# DRL.net
KiCad netlist of a schematic drawn in EAGLE
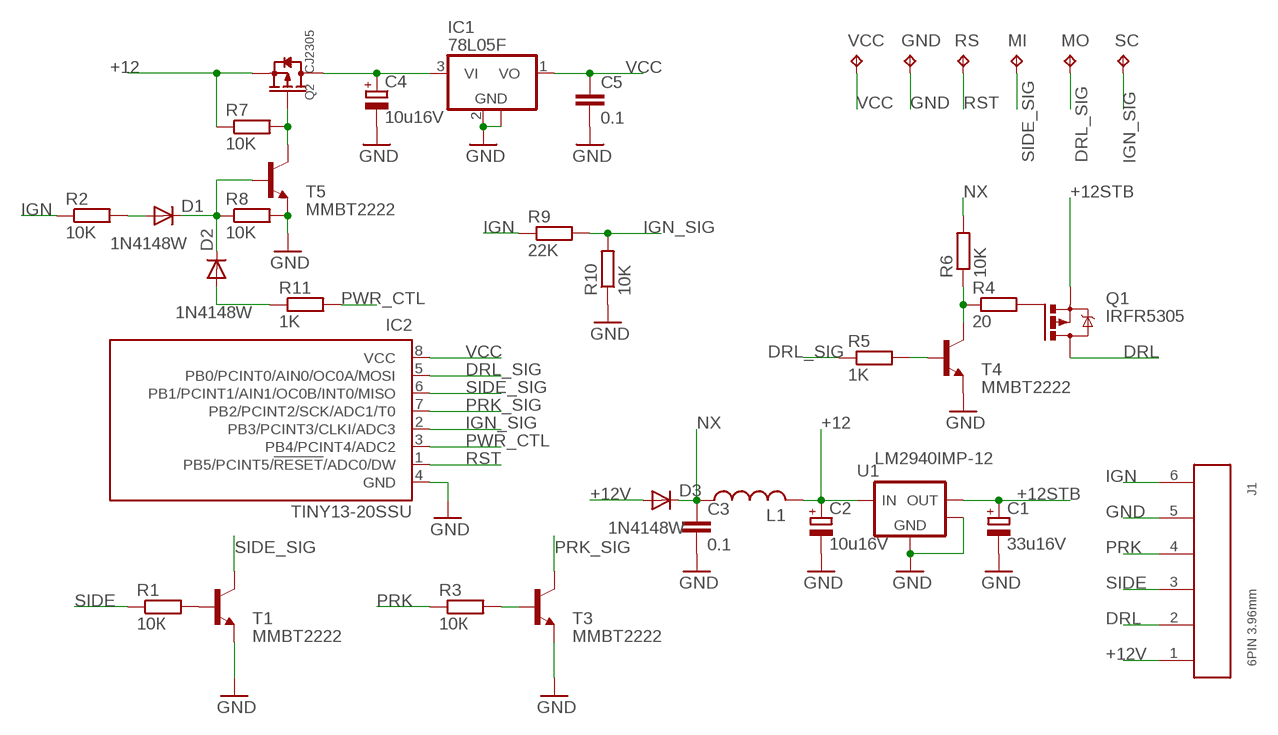
[diagram p0: schematic, sheet 1]

(export (version "E")
  (design (tool "Eeschema 10.0.6"))
  (components
    (comp (ref "C1")
      (value "33u16V")
      (footprint "eagle-import:SMC_B")
      (libsource (lib "eagle-import") (part "CPOL-EUSMCB"))
    )
    (comp (ref "C2")
      (value "10u16V")
      (footprint "eagle-import:SMC_B")
      (libsource (lib "eagle-import") (part "CPOL-EUSMCB"))
    )
    (comp (ref "C3")
      (value "0.1")
      (footprint "eagle-import:C0805")
      (libsource (lib "eagle-import") (part "C-EUC0805"))
    )
    (comp (ref "C4")
      (value "10u16V")
      (footprint "eagle-import:SMC_B")
      (libsource (lib "eagle-import") (part "CPOL-EUSMCB"))
    )
    (comp (ref "C5")
      (value "0.1")
      (footprint "eagle-import:C0805")
      (libsource (lib "eagle-import") (part "C-EUC0805"))
    )
    (comp (ref "D1")
      (value "1N4148W")
      (footprint "eagle-import:DO214AC")
      (libsource (lib "eagle-import") (part "DIODE-DO214AC"))
    )
    (comp (ref "D2")
      (value "1N4148W")
      (footprint "eagle-import:DO214AC")
      (libsource (lib "eagle-import") (part "DIODE-DO214AC"))
    )
    (comp (ref "D3")
      (value "1N4148W")
      (footprint "eagle-import:DO214AC")
      (libsource (lib "eagle-import") (part "DIODE-DO214AC"))
    )
    (comp (ref "GND")
      (value "TPB2,54")
      (footprint "eagle-import:B2,54")
      (libsource (lib "eagle-import") (part "TPB2,54"))
    )
    (comp (ref "IC1")
      (value "78L05F")
      (footprint "eagle-import:SOT89")
      (libsource (lib "eagle-import") (part "78LF05"))
    )
    (comp (ref "IC2")
      (value "TINY13-20SSU")
      (footprint "eagle-import:8S1")
      (fields (field (name "MPN") "ATTINY13-20SSU"))
      (libsource (lib "eagle-import") (part "TINY13SSU-20"))
    )
    (comp (ref "J1")
      (value "6PIN 3.96mm")
      (footprint "eagle-import:645006114822")
      (libsource (lib "eagle-import") (part "645006114822"))
    )
    (comp (ref "L1")
      (value "L-USL5038P")
      (footprint "eagle-import:L5038P")
      (libsource (lib "eagle-import") (part "L-USL5038P"))
    )
    (comp (ref "MI")
      (value "TPB2,54")
      (footprint "eagle-import:B2,54")
      (libsource (lib "eagle-import") (part "TPB2,54"))
    )
    (comp (ref "MO")
      (value "TPB2,54")
      (footprint "eagle-import:B2,54")
      (libsource (lib "eagle-import") (part "TPB2,54"))
    )
    (comp (ref "Q1")
      (value "IRFR5305")
      (footprint "eagle-import:D-PAK_TO252AA")
      (libsource (lib "eagle-import") (part "IRF?5305R"))
    )
    (comp (ref "Q2")
      (value "CJ2305")
      (footprint "eagle-import:SOT-23")
      (libsource (lib "eagle-import") (part "SMD-MOSFET-P-CH-8V-4.1A-CJ2305(SOT-23)"))
    )
    (comp (ref "R1")
      (value "10К")
      (footprint "eagle-import:R0805W")
      (libsource (lib "eagle-import") (part "R-EU_R0805W"))
    )
    (comp (ref "R2")
      (value "10K")
      (footprint "eagle-import:R0805W")
      (libsource (lib "eagle-import") (part "R-EU_R0805W"))
    )
    (comp (ref "R3")
      (value "10К")
      (footprint "eagle-import:R0805W")
      (libsource (lib "eagle-import") (part "R-EU_R0805W"))
    )
    (comp (ref "R4")
      (value "20")
      (footprint "eagle-import:R0805W")
      (libsource (lib "eagle-import") (part "R-EU_R0805W"))
    )
    (comp (ref "R5")
      (value "1K")
      (footprint "eagle-import:R0805W")
      (libsource (lib "eagle-import") (part "R-EU_R0805W"))
    )
    (comp (ref "R6")
      (value "10K")
      (footprint "eagle-import:R0805W")
      (libsource (lib "eagle-import") (part "R-EU_R0805W"))
    )
    (comp (ref "R7")
      (value "10K")
      (footprint "eagle-import:R0805W")
      (libsource (lib "eagle-import") (part "R-EU_R0805W"))
    )
    (comp (ref "R8")
      (value "10K")
      (footprint "eagle-import:R0805W")
      (libsource (lib "eagle-import") (part "R-EU_R0805W"))
    )
    (comp (ref "R9")
      (value "22K")
      (footprint "eagle-import:R0805W")
      (libsource (lib "eagle-import") (part "R-EU_R0805W"))
    )
    (comp (ref "R10")
      (value "10K")
      (footprint "eagle-import:R0805W")
      (libsource (lib "eagle-import") (part "R-EU_R0805W"))
    )
    (comp (ref "R11")
      (value "1K")
      (footprint "eagle-import:R0805W")
      (libsource (lib "eagle-import") (part "R-EU_R0805W"))
    )
    (comp (ref "RS")
      (value "TPB2,54")
      (footprint "eagle-import:B2,54")
      (libsource (lib "eagle-import") (part "TPB2,54"))
    )
    (comp (ref "SC")
      (value "TPB2,54")
      (footprint "eagle-import:B2,54")
      (libsource (lib "eagle-import") (part "TPB2,54"))
    )
    (comp (ref "T1")
      (value "MMBT2222")
      (footprint "eagle-import:SOT23-BEC")
      (libsource (lib "eagle-import") (part "-NPN-SOT23-BECMMBT2222ALT1"))
    )
    (comp (ref "T3")
      (value "MMBT2222")
      (footprint "eagle-import:SOT23-BEC")
      (libsource (lib "eagle-import") (part "-NPN-SOT23-BECMMBT2222ALT1"))
    )
    (comp (ref "T4")
      (value "MMBT2222")
      (footprint "eagle-import:SOT23-BEC")
      (libsource (lib "eagle-import") (part "-NPN-SOT23-BECMMBT2222ALT1"))
    )
    (comp (ref "T5")
      (value "MMBT2222")
      (footprint "eagle-import:SOT23-BEC")
      (libsource (lib "eagle-import") (part "-NPN-SOT23-BECMMBT2222ALT1"))
    )
    (comp (ref "U1")
      (value "LM2940IMP-12")
      (footprint "eagle-import:SOT-223-3")
      (libsource (lib "eagle-import") (part "LM2940DCY"))
    )
    (comp (ref "VCC")
      (value "TPB2,54")
      (footprint "eagle-import:B2,54")
      (libsource (lib "eagle-import") (part "TPB2,54"))
    )
  )
  (nets
    (net (code "1") (name "/+12") (class "Default")
      (node (ref "C2") (pin "+") (pinfunction "+_+") (pintype "passive"))
      (node (ref "L1") (pin "2") (pinfunction "2_2") (pintype "passive"))
      (node (ref "Q2") (pin "2") (pinfunction "S_2") (pintype "passive"))
      (node (ref "R7") (pin "1") (pinfunction "1_1") (pintype "passive"))
      (node (ref "U1") (pin "1") (pinfunction "VIN_1") (pintype "power_in"))
    )
    (net (code "2") (name "/+12STB") (class "Default")
      (node (ref "C1") (pin "+") (pinfunction "+_+") (pintype "passive"))
      (node (ref "Q1") (pin "3") (pinfunction "S_3") (pintype "passive"))
      (node (ref "U1") (pin "3") (pinfunction "VOUT_3") (pintype "power_in"))
    )
    (net (code "3") (name "/+12V") (class "Default")
      (node (ref "D3") (pin "A") (pinfunction "A_A") (pintype "passive"))
      (node (ref "J1") (pin "1") (pinfunction "1_1") (pintype "passive"))
    )
    (net (code "4") (name "/DRL") (class "Default")
      (node (ref "J1") (pin "2") (pinfunction "2_2") (pintype "passive"))
      (node (ref "Q1") (pin "4") (pinfunction "D_4") (pintype "passive"))
    )
    (net (code "5") (name "/DRL_SIG") (class "Default")
      (node (ref "IC2") (pin "5") (pinfunction "PB0/PCINT0/AIN0/OC0A/MOSI_5") (pintype "bidirectional"))
      (node (ref "MO") (pin "TP") (pinfunction "TP_TP") (pintype "input"))
      (node (ref "R5") (pin "1") (pinfunction "1_1") (pintype "passive"))
    )
    (net (code "6") (name "/IGN") (class "Default")
      (node (ref "J1") (pin "6") (pinfunction "6_6") (pintype "passive"))
      (node (ref "R2") (pin "1") (pinfunction "1_1") (pintype "passive"))
      (node (ref "R9") (pin "1") (pinfunction "1_1") (pintype "passive"))
    )
    (net (code "7") (name "/IGN_SIG") (class "Default")
      (node (ref "IC2") (pin "2") (pinfunction "PB3/PCINT3/CLKI/ADC3_2") (pintype "bidirectional"))
      (node (ref "R10") (pin "2") (pinfunction "2_2") (pintype "passive"))
      (node (ref "R9") (pin "2") (pinfunction "2_2") (pintype "passive"))
      (node (ref "SC") (pin "TP") (pinfunction "TP_TP") (pintype "input"))
    )
    (net (code "8") (name "/NX") (class "Default")
      (node (ref "C3") (pin "1") (pinfunction "1_1") (pintype "passive"))
      (node (ref "D3") (pin "C") (pinfunction "C_C") (pintype "passive"))
      (node (ref "L1") (pin "1") (pinfunction "1_1") (pintype "passive"))
      (node (ref "R6") (pin "2") (pinfunction "2_2") (pintype "passive"))
    )
    (net (code "9") (name "/PRK") (class "Default")
      (node (ref "J1") (pin "4") (pinfunction "4_4") (pintype "passive"))
      (node (ref "R3") (pin "1") (pinfunction "1_1") (pintype "passive"))
    )
    (net (code "10") (name "/PRK_SIG") (class "Default")
      (node (ref "IC2") (pin "7") (pinfunction "PB2/PCINT2/SCK/ADC1/T0_7") (pintype "bidirectional"))
      (node (ref "T3") (pin "C") (pinfunction "C_C") (pintype "passive"))
    )
    (net (code "11") (name "/PWR_CTL") (class "Default")
      (node (ref "IC2") (pin "3") (pinfunction "PB4/PCINT4/ADC2_3") (pintype "bidirectional"))
      (node (ref "R11") (pin "2") (pinfunction "2_2") (pintype "passive"))
    )
    (net (code "12") (name "/RST") (class "Default")
      (node (ref "IC2") (pin "1") (pinfunction "PB5/PCINT5/~{RESET}/ADC0/DW_1") (pintype "bidirectional"))
      (node (ref "RS") (pin "TP") (pinfunction "TP_TP") (pintype "input"))
    )
    (net (code "13") (name "/SIDE") (class "Default")
      (node (ref "J1") (pin "3") (pinfunction "3_3") (pintype "passive"))
      (node (ref "R1") (pin "1") (pinfunction "1_1") (pintype "passive"))
    )
    (net (code "14") (name "/SIDE_SIG") (class "Default")
      (node (ref "IC2") (pin "6") (pinfunction "PB1/PCINT1/AIN1/OC0B/INT0/MISO_6") (pintype "bidirectional"))
      (node (ref "MI") (pin "TP") (pinfunction "TP_TP") (pintype "input"))
      (node (ref "T1") (pin "C") (pinfunction "C_C") (pintype "passive"))
    )
    (net (code "15") (name "/VCC") (class "Default")
      (node (ref "C5") (pin "1") (pinfunction "1_1") (pintype "passive"))
      (node (ref "IC1") (pin "1") (pinfunction "VO_1") (pintype "passive"))
      (node (ref "IC2") (pin "8") (pinfunction "VCC_8") (pintype "power_in"))
      (node (ref "VCC") (pin "TP") (pinfunction "TP_TP") (pintype "input"))
    )
    (net (code "16") (name "GND") (class "Default")
      (node (ref "C1") (pin "-") (pinfunction "-_-") (pintype "passive"))
      (node (ref "C2") (pin "-") (pinfunction "-_-") (pintype "passive"))
      (node (ref "C3") (pin "2") (pinfunction "2_2") (pintype "passive"))
      (node (ref "C4") (pin "-") (pinfunction "-_-") (pintype "passive"))
      (node (ref "C5") (pin "2") (pinfunction "2_2") (pintype "passive"))
      (node (ref "GND") (pin "TP") (pinfunction "TP_TP") (pintype "input"))
      (node (ref "IC1") (pin "2") (pinfunction "GND_2") (pintype "passive"))
      (node (ref "IC1") (pin "2@1") (pinfunction "GND_2@1") (pintype "passive"))
      (node (ref "IC2") (pin "4") (pinfunction "GND_4") (pintype "power_in"))
      (node (ref "J1") (pin "5") (pinfunction "5_5") (pintype "passive"))
      (node (ref "R10") (pin "1") (pinfunction "1_1") (pintype "passive"))
      (node (ref "R8") (pin "2") (pinfunction "2_2") (pintype "passive"))
      (node (ref "T1") (pin "E") (pinfunction "E_E") (pintype "passive"))
      (node (ref "T3") (pin "E") (pinfunction "E_E") (pintype "passive"))
      (node (ref "T4") (pin "E") (pinfunction "E_E") (pintype "passive"))
      (node (ref "T5") (pin "E") (pinfunction "E_E") (pintype "passive"))
      (node (ref "U1") (pin "2") (pinfunction "GND_2") (pintype "power_in"))
      (node (ref "U1") (pin "4") (pinfunction "TAB_4") (pintype "power_in"))
    )
    (net (code "17") (name "Net-(D1-PadA)") (class "Default")
      (node (ref "D1") (pin "A") (pinfunction "A_A") (pintype "passive"))
      (node (ref "R2") (pin "2") (pinfunction "2_2") (pintype "passive"))
    )
    (net (code "18") (name "Net-(D1-PadC)") (class "Default")
      (node (ref "D1") (pin "C") (pinfunction "C_C") (pintype "passive"))
      (node (ref "D2") (pin "C") (pinfunction "C_C") (pintype "passive"))
      (node (ref "R8") (pin "1") (pinfunction "1_1") (pintype "passive"))
      (node (ref "T5") (pin "B") (pinfunction "B_B") (pintype "passive"))
    )
    (net (code "19") (name "Net-(D2-PadA)") (class "Default")
      (node (ref "D2") (pin "A") (pinfunction "A_A") (pintype "passive"))
      (node (ref "R11") (pin "1") (pinfunction "1_1") (pintype "passive"))
    )
    (net (code "20") (name "Net-(IC1-VI)") (class "Default")
      (node (ref "C4") (pin "+") (pinfunction "+_+") (pintype "passive"))
      (node (ref "IC1") (pin "3") (pinfunction "VI_3") (pintype "input"))
      (node (ref "Q2") (pin "3") (pinfunction "D_3") (pintype "passive"))
    )
    (net (code "21") (name "Net-(Q1-G)") (class "Default")
      (node (ref "Q1") (pin "1") (pinfunction "G_1") (pintype "passive"))
      (node (ref "R4") (pin "2") (pinfunction "2_2") (pintype "passive"))
    )
    (net (code "22") (name "Net-(Q2-G)") (class "Default")
      (node (ref "Q2") (pin "1") (pinfunction "G_1") (pintype "passive"))
      (node (ref "R7") (pin "2") (pinfunction "2_2") (pintype "passive"))
      (node (ref "T5") (pin "C") (pinfunction "C_C") (pintype "passive"))
    )
    (net (code "23") (name "Net-(R1-Pad2)") (class "Default")
      (node (ref "R1") (pin "2") (pinfunction "2_2") (pintype "passive"))
      (node (ref "T1") (pin "B") (pinfunction "B_B") (pintype "passive"))
    )
    (net (code "24") (name "Net-(R3-Pad2)") (class "Default")
      (node (ref "R3") (pin "2") (pinfunction "2_2") (pintype "passive"))
      (node (ref "T3") (pin "B") (pinfunction "B_B") (pintype "passive"))
    )
    (net (code "25") (name "Net-(R4-Pad1)") (class "Default")
      (node (ref "R4") (pin "1") (pinfunction "1_1") (pintype "passive"))
      (node (ref "R6") (pin "1") (pinfunction "1_1") (pintype "passive"))
      (node (ref "T4") (pin "C") (pinfunction "C_C") (pintype "passive"))
    )
    (net (code "26") (name "Net-(R5-Pad2)") (class "Default")
      (node (ref "R5") (pin "2") (pinfunction "2_2") (pintype "passive"))
      (node (ref "T4") (pin "B") (pinfunction "B_B") (pintype "passive"))
    )
  )
)
